# Pixel1_0_2.net
KiCad netlist of a schematic drawn in Altium Designer
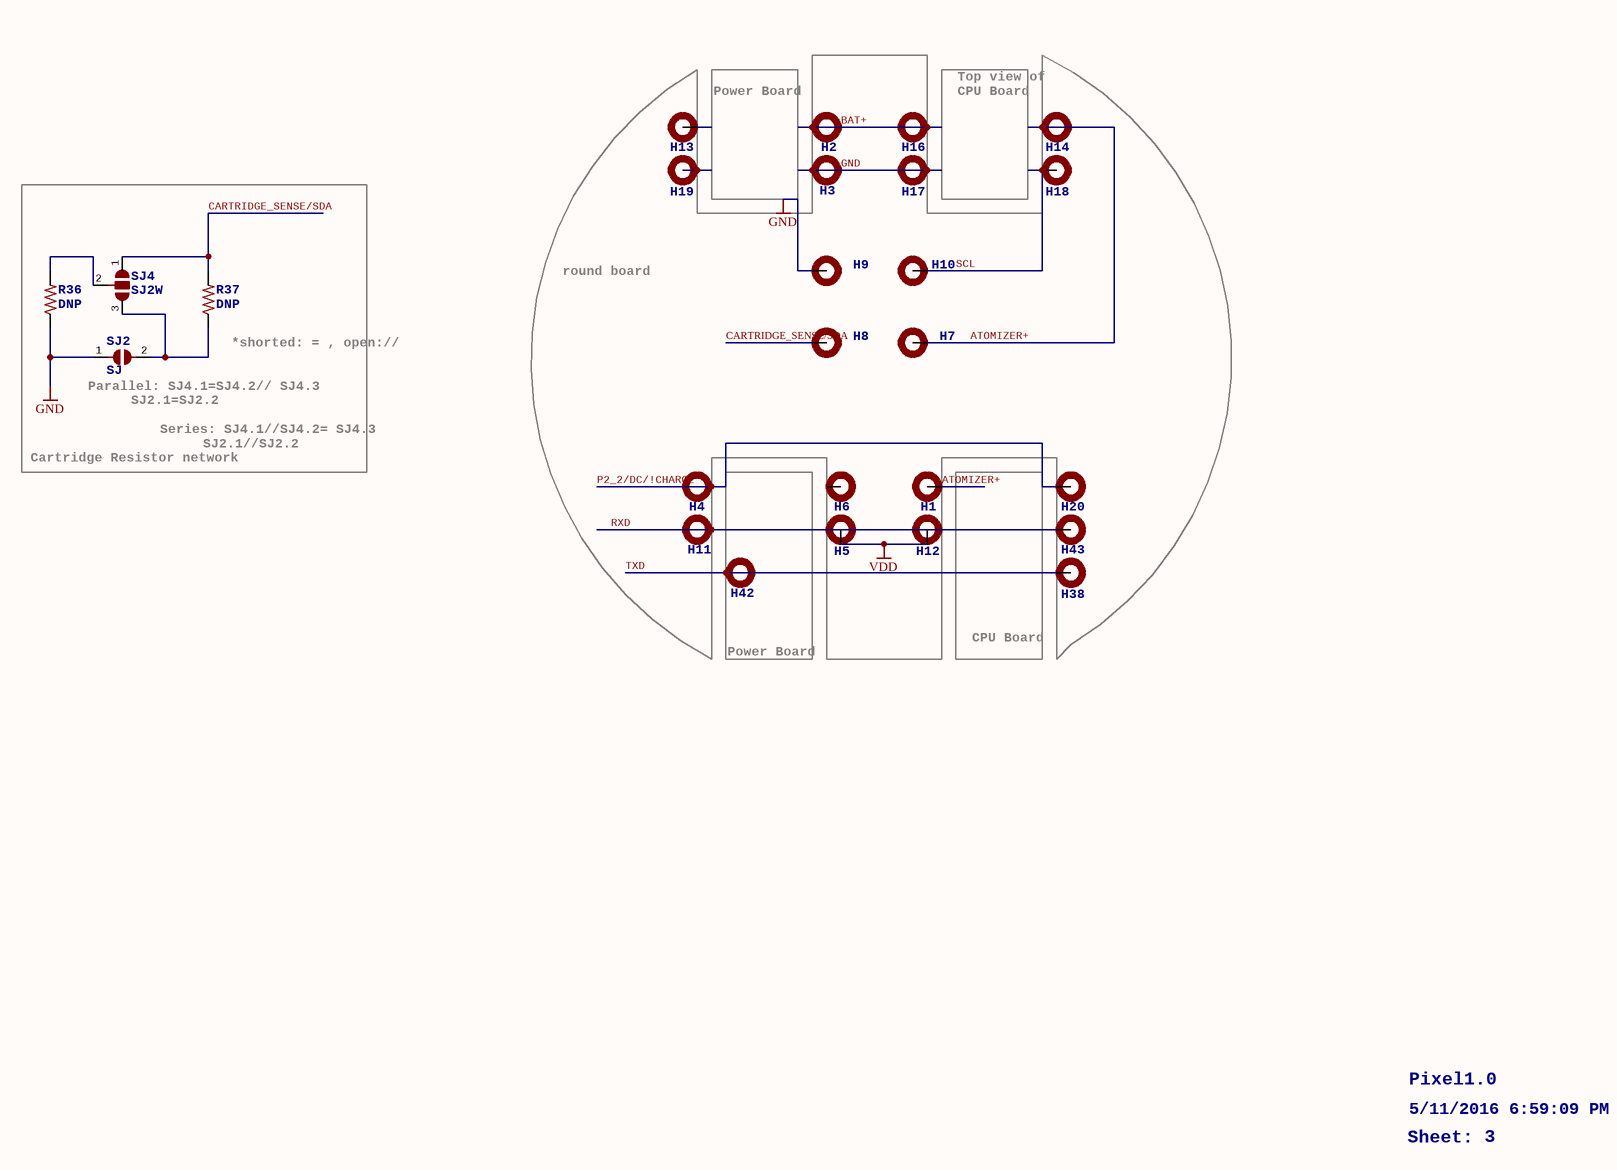
[diagram p0: Pixel1.0_2.SchDoc]

(export (version "E")
  (design (tool "Eeschema 10.0.6"))
  (components
    (comp (ref "H1")
      (value "MOUNT-PAD-ROUNDTMOUNT2")
      (footprint "TMOUNT2")
      (description "MOUNTING PAD, round")
      (libsource (lib "Pixel1.0") (part "MOUNT-PAD-ROUNDTMOUNT2"))
    )
    (comp (ref "H2")
      (value "MOUNT-PAD-ROUNDTMOUNT2")
      (footprint "TMOUNT2")
      (description "MOUNTING PAD, round")
      (libsource (lib "Pixel1.0") (part "MOUNT-PAD-ROUNDTMOUNT2"))
    )
    (comp (ref "H3")
      (value "MOUNT-PAD-ROUNDTMOUNT2")
      (footprint "TMOUNT2")
      (description "MOUNTING PAD, round")
      (libsource (lib "Pixel1.0") (part "MOUNT-PAD-ROUNDTMOUNT2"))
    )
    (comp (ref "H4")
      (value "MOUNT-PAD-ROUNDTMOUNT2")
      (footprint "TMOUNT2")
      (description "MOUNTING PAD, round")
      (libsource (lib "Pixel1.0") (part "MOUNT-PAD-ROUNDTMOUNT2"))
    )
    (comp (ref "H5")
      (value "MOUNT-PAD-ROUNDTMOUNT2")
      (footprint "TMOUNT2")
      (description "MOUNTING PAD, round")
      (libsource (lib "Pixel1.0") (part "MOUNT-PAD-ROUNDTMOUNT2"))
    )
    (comp (ref "H6")
      (value "MOUNT-PAD-ROUNDTMOUNT2")
      (footprint "TMOUNT2")
      (description "MOUNTING PAD, round")
      (libsource (lib "Pixel1.0") (part "MOUNT-PAD-ROUNDTMOUNT2"))
    )
    (comp (ref "H7")
      (value "MOUNT-PAD-ROUND2.8")
      (footprint "2,0-PAD")
      (description "MOUNTING PAD, round")
      (libsource (lib "Pixel1.0") (part "MOUNT-PAD-ROUND2.8"))
    )
    (comp (ref "H8")
      (value "MOUNT-PAD-ROUND2.8")
      (footprint "2,0-PAD")
      (description "MOUNTING PAD, round")
      (libsource (lib "Pixel1.0") (part "MOUNT-PAD-ROUND2.8"))
    )
    (comp (ref "H9")
      (value "MOUNT-PAD-ROUND2.8")
      (footprint "2,0-PAD")
      (description "MOUNTING PAD, round")
      (libsource (lib "Pixel1.0") (part "MOUNT-PAD-ROUND2.8"))
    )
    (comp (ref "H10")
      (value "MOUNT-PAD-ROUND2.8")
      (footprint "2,0-PAD")
      (description "MOUNTING PAD, round")
      (libsource (lib "Pixel1.0") (part "MOUNT-PAD-ROUND2.8"))
    )
    (comp (ref "H11")
      (value "MOUNT-PAD-ROUNDTRAPEZOID")
      (footprint "TMOUNT5")
      (description "MOUNTING PAD, round")
      (libsource (lib "Pixel1.0") (part "MOUNT-PAD-ROUNDTRAPEZOID"))
    )
    (comp (ref "H12")
      (value "MOUNT-PAD-ROUNDTMOUNT2")
      (footprint "TMOUNT2")
      (description "MOUNTING PAD, round")
      (libsource (lib "Pixel1.0") (part "MOUNT-PAD-ROUNDTMOUNT2"))
    )
    (comp (ref "H13")
      (value "MOUNT-PAD-ROUNDTMOUNT3")
      (footprint "TMOUNT3")
      (description "MOUNTING PAD, round")
      (libsource (lib "Pixel1.0") (part "MOUNT-PAD-ROUNDTMOUNT3"))
    )
    (comp (ref "H14")
      (value "MOUNT-PAD-ROUNDTMOUNT3")
      (footprint "TMOUNT3")
      (description "MOUNTING PAD, round")
      (libsource (lib "Pixel1.0") (part "MOUNT-PAD-ROUNDTMOUNT3"))
    )
    (comp (ref "H16")
      (value "MOUNT-PAD-ROUNDTMOUNT2")
      (footprint "TMOUNT2")
      (description "MOUNTING PAD, round")
      (libsource (lib "Pixel1.0") (part "MOUNT-PAD-ROUNDTMOUNT2"))
    )
    (comp (ref "H17")
      (value "MOUNT-PAD-ROUNDTMOUNT2")
      (footprint "TMOUNT2")
      (description "MOUNTING PAD, round")
      (libsource (lib "Pixel1.0") (part "MOUNT-PAD-ROUNDTMOUNT2"))
    )
    (comp (ref "H18")
      (value "MOUNT-PAD-ROUNDTMOUNT2")
      (footprint "TMOUNT2")
      (description "MOUNTING PAD, round")
      (libsource (lib "Pixel1.0") (part "MOUNT-PAD-ROUNDTMOUNT2"))
    )
    (comp (ref "H19")
      (value "MOUNT-PAD-ROUNDTMOUNT2")
      (footprint "TMOUNT2")
      (description "MOUNTING PAD, round")
      (libsource (lib "Pixel1.0") (part "MOUNT-PAD-ROUNDTMOUNT2"))
    )
    (comp (ref "H20")
      (value "MOUNT-PAD-ROUNDTMOUNT2")
      (footprint "TMOUNT2")
      (description "MOUNTING PAD, round")
      (libsource (lib "Pixel1.0") (part "MOUNT-PAD-ROUNDTMOUNT2"))
    )
    (comp (ref "H38")
      (value "MOUNT-PAD-ROUNDTRAPEZOID")
      (footprint "TMOUNT5")
      (description "MOUNTING PAD, round")
      (libsource (lib "Pixel1.0") (part "MOUNT-PAD-ROUNDTRAPEZOID"))
    )
    (comp (ref "H42")
      (value "MOUNT-PAD-ROUNDMIRROR")
      (footprint "TMOUNTTRAPMIRROR")
      (description "MOUNTING PAD, round")
      (libsource (lib "Pixel1.0") (part "MOUNT-PAD-ROUNDMIRROR"))
    )
    (comp (ref "H43")
      (value "MOUNT-PAD-ROUNDMIRROR")
      (footprint "TMOUNTTRAPMIRROR")
      (description "MOUNTING PAD, round")
      (libsource (lib "Pixel1.0") (part "MOUNT-PAD-ROUNDMIRROR"))
    )
    (comp (ref "R36")
      (value "DNP")
      (footprint "R0201")
      (description "RESISTOR, American symbol")
      (libsource (lib "rcl") (part "R-US_R0201"))
    )
    (comp (ref "R37")
      (value "DNP")
      (footprint "R0201")
      (description "RESISTOR, American symbol")
      (libsource (lib "rcl") (part "R-US_R0201"))
    )
    (comp (ref "SJ2")
      (value "SJ")
      (footprint "SJ")
      (description "SMD solder JUMPER")
      (libsource (lib "jumper") (part "SJ"))
    )
    (comp (ref "SJ4")
      (value "SJ2W")
      (footprint "SJ_2")
      (description "SMD solder JUMPER")
      (libsource (lib "jumper") (part "SJ2W"))
    )
  )
  (nets
    (net (code "1") (name "/ATOMIZER+") (class "Default")
      (node (ref "H1") (pin "1") (pinfunction "MOUNT_1") (pintype "passive"))
      (node (ref "H14") (pin "1") (pinfunction "MOUNT_1") (pintype "passive"))
      (node (ref "H7") (pin "1") (pinfunction "MOUNT_1") (pintype "passive"))
    )
    (net (code "2") (name "/BAT+") (class "Default")
      (node (ref "H16") (pin "1") (pinfunction "MOUNT_1") (pintype "passive"))
      (node (ref "H2") (pin "1") (pinfunction "MOUNT_1") (pintype "passive"))
    )
    (net (code "3") (name "/CARTRIDGE_SENSE{slash}SDA") (class "Default")
      (node (ref "H8") (pin "1") (pinfunction "MOUNT_1") (pintype "passive"))
      (node (ref "R37") (pin "2") (pinfunction "2_2") (pintype "passive"))
      (node (ref "SJ4") (pin "1") (pinfunction "1_1") (pintype "passive"))
    )
    (net (code "4") (name "/P2_2{slash}DC{slash}!CHARGE") (class "Default")
      (node (ref "H20") (pin "1") (pinfunction "MOUNT_1") (pintype "passive"))
      (node (ref "H4") (pin "1") (pinfunction "MOUNT_1") (pintype "passive"))
    )
    (net (code "5") (name "/RXD") (class "Default")
      (node (ref "H11") (pin "1") (pinfunction "MOUNT_1") (pintype "passive"))
      (node (ref "H43") (pin "1") (pinfunction "MOUNT_1") (pintype "passive"))
    )
    (net (code "6") (name "/SCL") (class "Default")
      (node (ref "H10") (pin "1") (pinfunction "MOUNT_1") (pintype "passive"))
      (node (ref "H18") (pin "1") (pinfunction "MOUNT_1") (pintype "passive"))
    )
    (net (code "7") (name "/TXD") (class "Default")
      (node (ref "H38") (pin "1") (pinfunction "MOUNT_1") (pintype "passive"))
      (node (ref "H42") (pin "1") (pinfunction "MOUNT_1") (pintype "passive"))
    )
    (net (code "8") (name "GND") (class "Default")
      (node (ref "H17") (pin "1") (pinfunction "MOUNT_1") (pintype "passive"))
      (node (ref "H3") (pin "1") (pinfunction "MOUNT_1") (pintype "passive"))
      (node (ref "H9") (pin "1") (pinfunction "MOUNT_1") (pintype "passive"))
      (node (ref "R36") (pin "1") (pinfunction "1_1") (pintype "passive"))
      (node (ref "SJ2") (pin "1") (pinfunction "1_1") (pintype "passive"))
    )
    (net (code "9") (name "Net-(R36-Pad2)") (class "Default")
      (node (ref "R36") (pin "2") (pinfunction "2_2") (pintype "passive"))
      (node (ref "SJ4") (pin "2") (pinfunction "2_2") (pintype "passive"))
    )
    (net (code "10") (name "Net-(R37-Pad1)") (class "Default")
      (node (ref "R37") (pin "1") (pinfunction "1_1") (pintype "passive"))
      (node (ref "SJ2") (pin "2") (pinfunction "2_2") (pintype "passive"))
      (node (ref "SJ4") (pin "3") (pinfunction "3_3") (pintype "passive"))
    )
    (net (code "11") (name "VDD") (class "Default")
      (node (ref "H12") (pin "1") (pinfunction "MOUNT_1") (pintype "passive"))
      (node (ref "H5") (pin "1") (pinfunction "MOUNT_1") (pintype "passive"))
    )
    (net (code "12") (name "unconnected-(H6-MOUNT-Pad1)") (class "Default")
      (node (ref "H6") (pin "1") (pinfunction "MOUNT_1") (pintype "passive"))
    )
    (net (code "13") (name "unconnected-(H13-MOUNT-Pad1)") (class "Default")
      (node (ref "H13") (pin "1") (pinfunction "MOUNT_1") (pintype "passive"))
    )
    (net (code "14") (name "unconnected-(H19-MOUNT-Pad1)") (class "Default")
      (node (ref "H19") (pin "1") (pinfunction "MOUNT_1") (pintype "passive"))
    )
  )
)
